# Power_Supply.net
KiCad netlist of a schematic drawn in Altium Designer
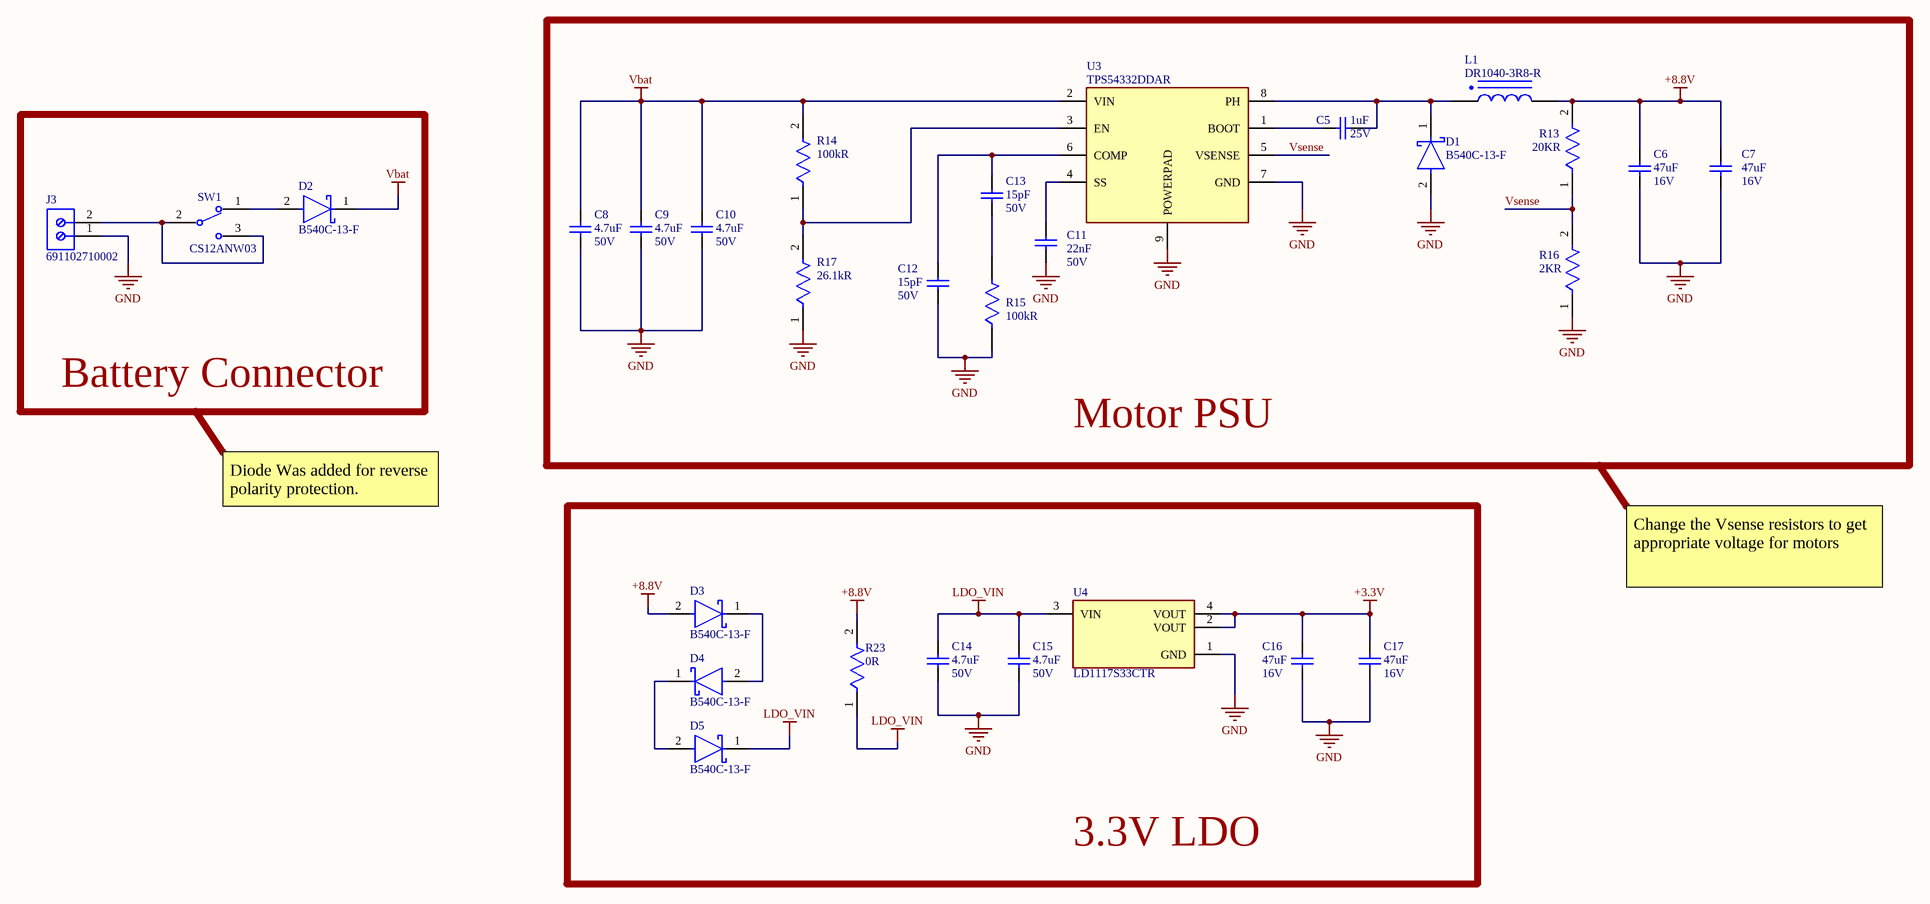
[diagram p0: Power Supply.SchDoc]

(export (version "E")
  (design (tool "Eeschema 10.0.6"))
  (components
    (comp (ref "C5")
      (value "1uF")
      (footprint "FP-CC0603-DA-IPC_B")
      (fields (field (name "VOLTAGE RATING") "25V") (field (name "Comment") "1uF 25V 0603"))
      (libsource (lib "2025 Bright Manufacturing Challenge") (part "CAP"))
    )
    (comp (ref "C6")
      (value "47uF")
      (footprint "FP-1210-L_3_2_0_3-W_2_5_0-MFG")
      (fields (field (name "VOLTAGE RATING") "16V") (field (name "Comment") "47uF 16V 1210"))
      (libsource (lib "2025 Bright Manufacturing Challenge") (part "CAP"))
    )
    (comp (ref "C7")
      (value "47uF")
      (footprint "FP-1210-L_3_2_0_3-W_2_5_0-MFG")
      (fields (field (name "VOLTAGE RATING") "16V") (field (name "Comment") "47uF 16V 1210"))
      (libsource (lib "2025 Bright Manufacturing Challenge") (part "CAP"))
    )
    (comp (ref "C8")
      (value "4.7uF")
      (footprint "FP-GRM21B-0_15-IPC_A")
      (fields (field (name "VOLTAGE RATING") "50V") (field (name "Comment") "4.7uF 50V 0805"))
      (libsource (lib "2025 Bright Manufacturing Challenge") (part "CAP"))
    )
    (comp (ref "C9")
      (value "4.7uF")
      (footprint "FP-GRM21B-0_15-IPC_A")
      (fields (field (name "VOLTAGE RATING") "50V") (field (name "Comment") "4.7uF 50V 0805"))
      (libsource (lib "2025 Bright Manufacturing Challenge") (part "CAP"))
    )
    (comp (ref "C10")
      (value "4.7uF")
      (footprint "FP-GRM21B-0_15-IPC_A")
      (fields (field (name "VOLTAGE RATING") "50V") (field (name "Comment") "4.7uF 50V 0805"))
      (libsource (lib "2025 Bright Manufacturing Challenge") (part "CAP"))
    )
    (comp (ref "C11")
      (value "22nF")
      (footprint "FP-C2012-125-0_2-IPC_A")
      (fields (field (name "VOLTAGE RATING") "50V") (field (name "Comment") ".022uF 50V 0805"))
      (libsource (lib "2025 Bright Manufacturing Challenge") (part "CAP"))
    )
    (comp (ref "C12")
      (value "15pF")
      (footprint "FP-CC0603-0_9-IPC_A")
      (fields (field (name "VOLTAGE RATING") "50V") (field (name "Comment") "15pF 50V 0603"))
      (libsource (lib "2025 Bright Manufacturing Challenge") (part "CAP"))
    )
    (comp (ref "C13")
      (value "15pF")
      (footprint "FP-CC0603-0_9-IPC_A")
      (fields (field (name "VOLTAGE RATING") "50V") (field (name "Comment") "15pF 50V 0603"))
      (libsource (lib "2025 Bright Manufacturing Challenge") (part "CAP"))
    )
    (comp (ref "C14")
      (value "4.7uF")
      (footprint "FP-GRM21B-0_15-IPC_A")
      (fields (field (name "RATED DC VOLTAGE (URDC)") "50V") (field (name "Comment") "4.7uF 50V 0805"))
      (libsource (lib "2025 Bright Manufacturing Challenge") (part "CAP"))
    )
    (comp (ref "C15")
      (value "4.7uF")
      (footprint "FP-GRM21B-0_15-IPC_A")
      (fields (field (name "RATED DC VOLTAGE (URDC)") "50V") (field (name "Comment") "4.7uF 50V 0805"))
      (libsource (lib "2025 Bright Manufacturing Challenge") (part "CAP"))
    )
    (comp (ref "C16")
      (value "47uF")
      (footprint "FP-1210-L_3_2_0_3-W_2_5_0-MFG")
      (fields (field (name "RATED DC VOLTAGE (URDC)") "16V") (field (name "Comment") "CAP"))
      (libsource (lib "2025 Bright Manufacturing Challenge") (part "CAP"))
    )
    (comp (ref "C17")
      (value "47uF")
      (footprint "FP-1210-L_3_2_0_3-W_2_5_0-MFG")
      (fields (field (name "RATED DC VOLTAGE (URDC)") "16V") (field (name "Comment") "CAP"))
      (libsource (lib "2025 Bright Manufacturing Challenge") (part "CAP"))
    )
    (comp (ref "D1")
      (value "B540C-13-F")
      (footprint "FP-SMC-MFG")
      (description "Rectifier Diode, Schottky, 1 Phase, 1 Element, 5A, 40V V(RRM), Silicon")
      (libsource (lib "2025 Bright Manufacturing Challenge") (part "1d6ec82d83fb6aee721767c19dac4b9"))
    )
    (comp (ref "D2")
      (value "B540C-13-F")
      (footprint "FP-SMC-MFG")
      (description "Rectifier Diode, Schottky, 1 Phase, 1 Element, 5A, 40V V(RRM), Silicon")
      (libsource (lib "2025 Bright Manufacturing Challenge") (part "1d6ec82d83fb6aee721767c19dac4b9"))
    )
    (comp (ref "D3")
      (value "B540C-13-F")
      (footprint "FP-SMC-MFG")
      (description "Rectifier Diode, Schottky, 1 Phase, 1 Element, 5A, 40V V(RRM), Silicon")
      (libsource (lib "2025 Bright Manufacturing Challenge") (part "1d6ec82d83fb6aee721767c19dac4b9"))
    )
    (comp (ref "D4")
      (value "B540C-13-F")
      (footprint "FP-SMC-MFG")
      (description "Rectifier Diode, Schottky, 1 Phase, 1 Element, 5A, 40V V(RRM), Silicon")
      (libsource (lib "2025 Bright Manufacturing Challenge") (part "1d6ec82d83fb6aee721767c19dac4b9"))
    )
    (comp (ref "D5")
      (value "B540C-13-F")
      (footprint "FP-SMC-MFG")
      (description "Rectifier Diode, Schottky, 1 Phase, 1 Element, 5A, 40V V(RRM), Silicon")
      (libsource (lib "2025 Bright Manufacturing Challenge") (part "1d6ec82d83fb6aee721767c19dac4b9"))
    )
    (comp (ref "J3")
      (value "691102710002")
      (footprint "691102710002")
      (description "Barrier Strip Terminal Block")
      (libsource (lib "2025 Bright Manufacturing Challenge") (part "TBL - 1R - 02P - Screw"))
    )
    (comp (ref "L1")
      (value "DR1040-3R8-R")
      (footprint "DR1040-3R8-R-Footprint-1")
      (description "General Purpose Inductor, 3.8uH, 30%, 1 Element, Ferrite-Core, SMD, 4141")
      (fields (field (name "TOLERANCE") "30%"))
      (libsource (lib "2025 Bright Manufacturing Challenge") (part "DR1040-3R8-R-Symbol-1"))
    )
    (comp (ref "R13")
      (value "20KR")
      (footprint "FP-RC0603-0_55-IPC_C")
      (description "RES 20K OHM 1% 1/10W 0603")
      (fields (field (name "TOLERANCE") "1%"))
      (libsource (lib "Altium Content Vault") (part "1029c3af85768c4190bb7ad29bc67b5"))
    )
    (comp (ref "R14")
      (value "100kR")
      (footprint "FP-RC0603-0_55-IPC_C")
      (fields
        (field (name "TOLERANCE") "1%")
        (field (name "POWER") "100mW")
        (field (name "Comment") "100Kohm 0603")
      )
      (libsource (lib "2025 Bright Manufacturing Challenge") (part "1029c3af85768c4190bb7ad29bc67b5"))
    )
    (comp (ref "R15")
      (value "100kR")
      (footprint "FP-RC0603-0_55-IPC_C")
      (fields
        (field (name "TOLERANCE") "1%")
        (field (name "POWER") "100mW")
        (field (name "Comment") "100Kohm 0603")
      )
      (libsource (lib "") (part "1029c3af85768c4190bb7ad29bc67b5_1"))
    )
    (comp (ref "R16")
      (value "2KR")
      (footprint "FP-AC0603-IPC_B")
      (description "RES 2kΩ 1.00% 0.1W 0603")
      (fields (field (name "TOLERANCE") "1%"))
      (libsource (lib "Altium Content Vault") (part "1029c3af85768c4190bb7ad29bc67b5"))
    )
    (comp (ref "R17")
      (value "26.1kR")
      (footprint "FP-RT0603-IPC_C")
      (description "Fixed Resistor, Thin Film, 0.1W, 26100ohm, 75V, 0.1% +/-Tol, 25ppm/Cel, Surface Mount, 0603")
      (fields (field (name "TOLERANCE") "0.1%") (field (name "POWER") "100mW"))
      (libsource (lib "2025 Bright Manufacturing Challenge") (part "1029c3af85768c4190bb7ad29bc67b5"))
    )
    (comp (ref "R23")
      (value "0R")
      (footprint "FP-RC0603-MFG")
      (description "RES SMD 0 OHM JUMPER 1/10W 0603")
      (fields
        (field (name "TOLERANCE") "1%")
        (field (name "OCTOPART") "https://octopart.com/rc0603fr-070rl-yageo-1180803")
      )
      (libsource (lib "Altium Content Vault") (part "1029c3af85768c4190bb7ad29bc67b5"))
    )
    (comp (ref "SW1")
      (value "CS12ANW03")
      (footprint "FP-CS12ANW03-MFG")
      (description "Slide Switch")
      (libsource (lib "2025 Bright Manufacturing Challenge") (part "12161840acc88c497b895bf2e19a5b1"))
    )
    (comp (ref "U3")
      (value "TPS54332DDAR")
      (footprint "SOIC127P600X170-9N")
      (description "Switching Regulator, Current-mode, 3.5A, 1000kHz Switching Freq-Max, PDSO8")
      (libsource (lib "2025 Bright Manufacturing Challenge") (part "TPS54332DDAR-Symbol-1"))
    )
    (comp (ref "U4")
      (value "LD1117S33CTR")
      (footprint "FP-SOT-223-0046067_14-MFG")
      (description "Fixed Positive LDO Regulator, 3.3V, 1.3V Dropout, BIPolar, PDSO4")
      (libsource (lib "2025 Bright Manufacturing Challenge") (part "7818869c5c16ceab15634627166a29d"))
    )
  )
  (nets
    (net (code "1") (name "+3.3V") (class "Default")
      (node (ref "C16") (pin "2") (pinfunction "2_2") (pintype "passive"))
      (node (ref "C17") (pin "2") (pinfunction "2_2") (pintype "passive"))
      (node (ref "U4") (pin "2") (pinfunction "VOUT_2") (pintype "power_in"))
      (node (ref "U4") (pin "4") (pinfunction "VOUT_4") (pintype "power_in"))
    )
    (net (code "2") (name "+8.8V") (class "Default")
      (node (ref "C6") (pin "2") (pinfunction "2_2") (pintype "passive"))
      (node (ref "C7") (pin "2") (pinfunction "2_2") (pintype "passive"))
      (node (ref "D3") (pin "2") (pinfunction "A_2") (pintype "passive"))
      (node (ref "L1") (pin "2") (pinfunction "2_2") (pintype "passive"))
      (node (ref "R13") (pin "2") (pinfunction "2_2") (pintype "passive"))
      (node (ref "R23") (pin "2") (pinfunction "2_2") (pintype "passive"))
    )
    (net (code "3") (name "/Vsense") (class "Default")
      (node (ref "R13") (pin "1") (pinfunction "1_1") (pintype "passive"))
      (node (ref "R16") (pin "2") (pinfunction "2_2") (pintype "passive"))
      (node (ref "U3") (pin "5") (pinfunction "VSENSE_5") (pintype "passive"))
    )
    (net (code "4") (name "GND") (class "Default")
      (node (ref "C10") (pin "1") (pinfunction "1_1") (pintype "passive"))
      (node (ref "C11") (pin "1") (pinfunction "1_1") (pintype "passive"))
      (node (ref "C12") (pin "1") (pinfunction "1_1") (pintype "passive"))
      (node (ref "C14") (pin "1") (pinfunction "1_1") (pintype "passive"))
      (node (ref "C15") (pin "1") (pinfunction "1_1") (pintype "passive"))
      (node (ref "C16") (pin "1") (pinfunction "1_1") (pintype "passive"))
      (node (ref "C17") (pin "1") (pinfunction "1_1") (pintype "passive"))
      (node (ref "C6") (pin "1") (pinfunction "1_1") (pintype "passive"))
      (node (ref "C7") (pin "1") (pinfunction "1_1") (pintype "passive"))
      (node (ref "C8") (pin "1") (pinfunction "1_1") (pintype "passive"))
      (node (ref "C9") (pin "1") (pinfunction "1_1") (pintype "passive"))
      (node (ref "D1") (pin "2") (pinfunction "A_2") (pintype "passive"))
      (node (ref "J3") (pin "1") (pinfunction "1_1") (pintype "passive"))
      (node (ref "R15") (pin "1") (pinfunction "1_1") (pintype "passive"))
      (node (ref "R16") (pin "1") (pinfunction "1_1") (pintype "passive"))
      (node (ref "R17") (pin "1") (pinfunction "1_1") (pintype "passive"))
      (node (ref "U3") (pin "7") (pinfunction "GND_7") (pintype "passive"))
      (node (ref "U3") (pin "9") (pinfunction "POWERPAD_9") (pintype "passive"))
      (node (ref "U4") (pin "1") (pinfunction "GND_1") (pintype "power_in"))
    )
    (net (code "5") (name "LDO_VIN") (class "Default")
      (node (ref "C14") (pin "2") (pinfunction "2_2") (pintype "passive"))
      (node (ref "C15") (pin "2") (pinfunction "2_2") (pintype "passive"))
      (node (ref "D5") (pin "1") (pinfunction "C_1") (pintype "passive"))
      (node (ref "R23") (pin "1") (pinfunction "1_1") (pintype "passive"))
      (node (ref "U4") (pin "3") (pinfunction "VIN_3") (pintype "power_in"))
    )
    (net (code "6") (name "Net-(C13-Pad1)") (class "Default")
      (node (ref "C13") (pin "1") (pinfunction "1_1") (pintype "passive"))
      (node (ref "R15") (pin "2") (pinfunction "2_2") (pintype "passive"))
    )
    (net (code "7") (name "Net-(D1-C)") (class "Default")
      (node (ref "C5") (pin "1") (pinfunction "1_1") (pintype "passive"))
      (node (ref "D1") (pin "1") (pinfunction "C_1") (pintype "passive"))
      (node (ref "L1") (pin "1") (pinfunction "1_1") (pintype "passive"))
      (node (ref "U3") (pin "8") (pinfunction "PH_8") (pintype "passive"))
    )
    (net (code "8") (name "Net-(D2-A)") (class "Default")
      (node (ref "D2") (pin "2") (pinfunction "A_2") (pintype "passive"))
      (node (ref "SW1") (pin "1") (pinfunction "1_1") (pintype "passive"))
    )
    (net (code "9") (name "Net-(D3-C)") (class "Default")
      (node (ref "D3") (pin "1") (pinfunction "C_1") (pintype "passive"))
      (node (ref "D4") (pin "2") (pinfunction "A_2") (pintype "passive"))
    )
    (net (code "10") (name "Net-(D4-C)") (class "Default")
      (node (ref "D4") (pin "1") (pinfunction "C_1") (pintype "passive"))
      (node (ref "D5") (pin "2") (pinfunction "A_2") (pintype "passive"))
    )
    (net (code "11") (name "Net-(SW1-2(COM))") (class "Default")
      (node (ref "J3") (pin "2") (pinfunction "2_2") (pintype "passive"))
      (node (ref "SW1") (pin "2") (pinfunction "2(COM)_2") (pintype "passive"))
      (node (ref "SW1") (pin "3") (pinfunction "3_3") (pintype "passive"))
    )
    (net (code "12") (name "Net-(U3-BOOT)") (class "Default")
      (node (ref "C5") (pin "2") (pinfunction "2_2") (pintype "passive"))
      (node (ref "U3") (pin "1") (pinfunction "BOOT_1") (pintype "passive"))
    )
    (net (code "13") (name "Net-(U3-COMP)") (class "Default")
      (node (ref "C12") (pin "2") (pinfunction "2_2") (pintype "passive"))
      (node (ref "C13") (pin "2") (pinfunction "2_2") (pintype "passive"))
      (node (ref "U3") (pin "6") (pinfunction "COMP_6") (pintype "passive"))
    )
    (net (code "14") (name "Net-(U3-EN)") (class "Default")
      (node (ref "R14") (pin "1") (pinfunction "1_1") (pintype "passive"))
      (node (ref "R17") (pin "2") (pinfunction "2_2") (pintype "passive"))
      (node (ref "U3") (pin "3") (pinfunction "EN_3") (pintype "passive"))
    )
    (net (code "15") (name "Net-(U3-SS)") (class "Default")
      (node (ref "C11") (pin "2") (pinfunction "2_2") (pintype "passive"))
      (node (ref "U3") (pin "4") (pinfunction "SS_4") (pintype "passive"))
    )
    (net (code "16") (name "Vbat") (class "Default")
      (node (ref "C10") (pin "2") (pinfunction "2_2") (pintype "passive"))
      (node (ref "C8") (pin "2") (pinfunction "2_2") (pintype "passive"))
      (node (ref "C9") (pin "2") (pinfunction "2_2") (pintype "passive"))
      (node (ref "D2") (pin "1") (pinfunction "C_1") (pintype "passive"))
      (node (ref "R14") (pin "2") (pinfunction "2_2") (pintype "passive"))
      (node (ref "U3") (pin "2") (pinfunction "VIN_2") (pintype "passive"))
    )
  )
)
